# BoardC.net
KiCad netlist of a schematic drawn in Altium Designer
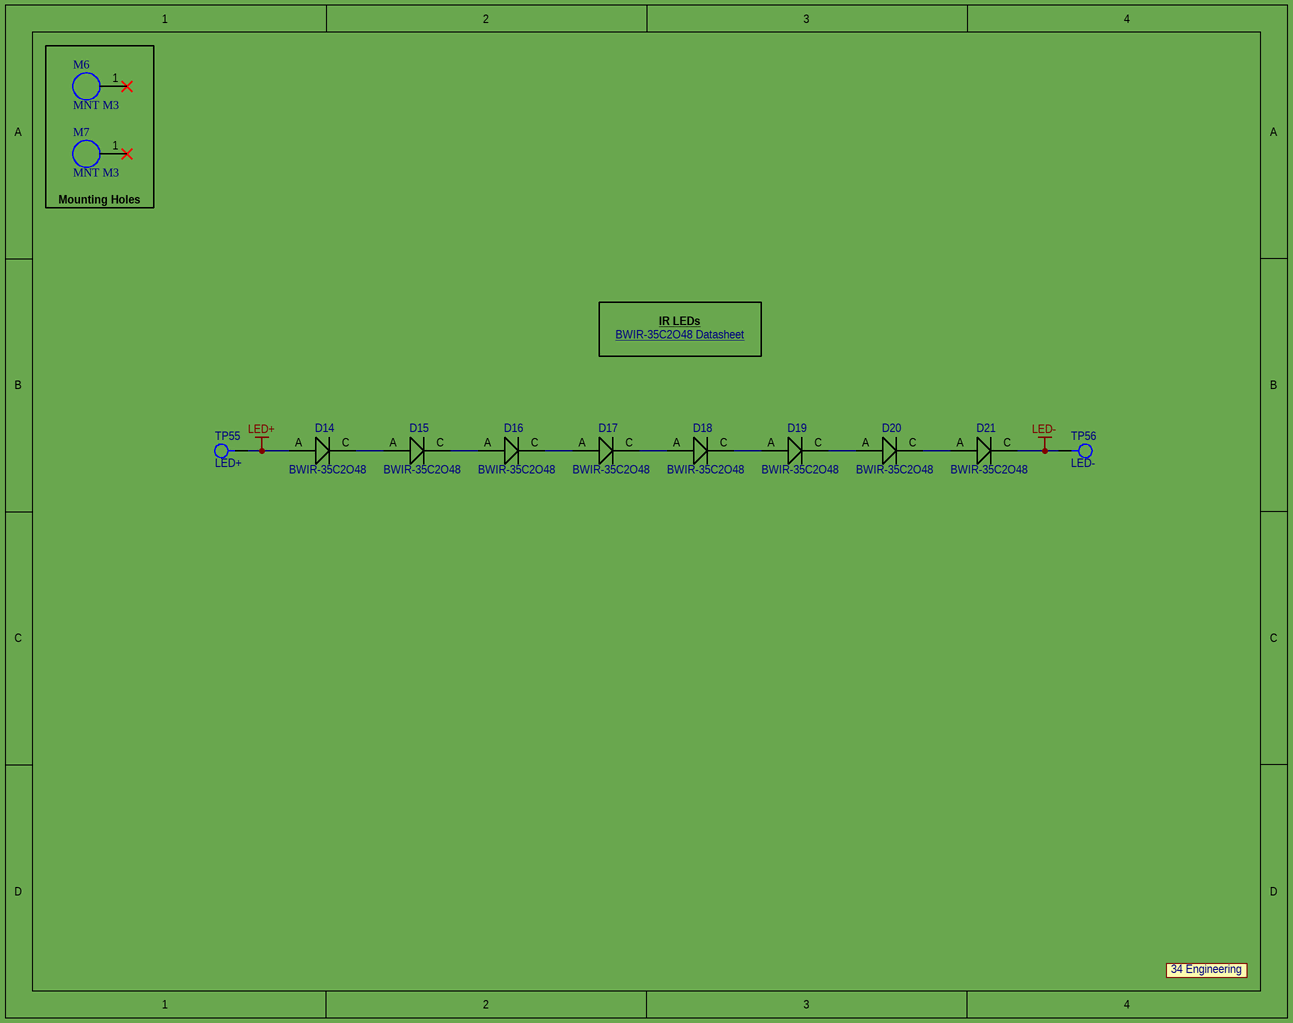
[diagram p0: BoardC.SchDoc]

(export (version "E")
  (design (tool "Eeschema 10.0.6"))
  (components
    (comp (ref "D14")
      (value "BWIR-35C2O48")
      (footprint "BWIR-35C2O48")
      (description "Infrared (IR) Emitter 850nm 1.7V 1A 260mW/sr @ 1A (Typ) 120° 1414 (3535 Metric)")
      (fields (field (name "MANUFACTURER") "American Bright"))
      (libsource (lib "Virtex") (part "BWIR-35C2O48"))
    )
    (comp (ref "D15")
      (value "BWIR-35C2O48")
      (footprint "BWIR-35C2O48")
      (description "Infrared (IR) Emitter 850nm 1.7V 1A 260mW/sr @ 1A (Typ) 120° 1414 (3535 Metric)")
      (fields (field (name "MANUFACTURER") "American Bright"))
      (libsource (lib "Virtex") (part "BWIR-35C2O48"))
    )
    (comp (ref "D16")
      (value "BWIR-35C2O48")
      (footprint "BWIR-35C2O48")
      (description "Infrared (IR) Emitter 850nm 1.7V 1A 260mW/sr @ 1A (Typ) 120° 1414 (3535 Metric)")
      (fields (field (name "MANUFACTURER") "American Bright"))
      (libsource (lib "Virtex") (part "BWIR-35C2O48"))
    )
    (comp (ref "D17")
      (value "BWIR-35C2O48")
      (footprint "BWIR-35C2O48")
      (description "Infrared (IR) Emitter 850nm 1.7V 1A 260mW/sr @ 1A (Typ) 120° 1414 (3535 Metric)")
      (fields (field (name "MANUFACTURER") "American Bright"))
      (libsource (lib "Virtex") (part "BWIR-35C2O48"))
    )
    (comp (ref "D18")
      (value "BWIR-35C2O48")
      (footprint "BWIR-35C2O48")
      (description "Infrared (IR) Emitter 850nm 1.7V 1A 260mW/sr @ 1A (Typ) 120° 1414 (3535 Metric)")
      (fields (field (name "MANUFACTURER") "American Bright"))
      (libsource (lib "Virtex") (part "BWIR-35C2O48"))
    )
    (comp (ref "D19")
      (value "BWIR-35C2O48")
      (footprint "BWIR-35C2O48")
      (description "Infrared (IR) Emitter 850nm 1.7V 1A 260mW/sr @ 1A (Typ) 120° 1414 (3535 Metric)")
      (fields (field (name "MANUFACTURER") "American Bright"))
      (libsource (lib "Virtex") (part "BWIR-35C2O48"))
    )
    (comp (ref "D20")
      (value "BWIR-35C2O48")
      (footprint "BWIR-35C2O48")
      (description "Infrared (IR) Emitter 850nm 1.7V 1A 260mW/sr @ 1A (Typ) 120° 1414 (3535 Metric)")
      (fields (field (name "MANUFACTURER") "American Bright"))
      (libsource (lib "Virtex") (part "BWIR-35C2O48"))
    )
    (comp (ref "D21")
      (value "BWIR-35C2O48")
      (footprint "BWIR-35C2O48")
      (description "Infrared (IR) Emitter 850nm 1.7V 1A 260mW/sr @ 1A (Typ) 120° 1414 (3535 Metric)")
      (fields (field (name "MANUFACTURER") "American Bright"))
      (libsource (lib "Virtex") (part "BWIR-35C2O48"))
    )
    (comp (ref "LOGO2")
      (value "34 Engineering Logo")
      (footprint "34EngineeringLogo")
      (description "34 Engineering Silkscreen Logo")
      (libsource (lib "Virtex") (part "34EngineeringLogo"))
    )
    (comp (ref "M6")
      (value "MNT M3")
      (footprint "MNT M3")
      (description "Mounting hole for an M3 bolt")
      (libsource (lib "Virtex") (part "MNT M3"))
    )
    (comp (ref "M7")
      (value "MNT M3")
      (footprint "MNT M3")
      (description "Mounting hole for an M3 bolt")
      (libsource (lib "Virtex") (part "MNT M3"))
    )
    (comp (ref "TP55")
      (value "LED+")
      (footprint "TestPoint1mm")
      (description "Test Point 1mm Diameter")
      (libsource (lib "Virtex") (part "TestPoint1mm"))
    )
    (comp (ref "TP56")
      (value "LED-")
      (footprint "TestPoint1mm")
      (description "Test Point 1mm Diameter")
      (libsource (lib "Virtex") (part "TestPoint1mm"))
    )
  )
  (nets
    (net (code "1") (name "LED+") (class "Default")
      (node (ref "D14") (pin "A") (pintype "power_in"))
      (node (ref "TP55") (pin "1") (pintype "passive"))
    )
    (net (code "2") (name "LED-") (class "Default")
      (node (ref "D21") (pin "C") (pintype "power_in"))
      (node (ref "TP56") (pin "1") (pintype "passive"))
    )
    (net (code "3") (name "Net-(D14-PadC)") (class "Default")
      (node (ref "D14") (pin "C") (pintype "power_in"))
      (node (ref "D15") (pin "A") (pintype "power_in"))
    )
    (net (code "4") (name "Net-(D15-PadC)") (class "Default")
      (node (ref "D15") (pin "C") (pintype "power_in"))
      (node (ref "D16") (pin "A") (pintype "power_in"))
    )
    (net (code "5") (name "Net-(D16-PadC)") (class "Default")
      (node (ref "D16") (pin "C") (pintype "power_in"))
      (node (ref "D17") (pin "A") (pintype "power_in"))
    )
    (net (code "6") (name "Net-(D17-PadC)") (class "Default")
      (node (ref "D17") (pin "C") (pintype "power_in"))
      (node (ref "D18") (pin "A") (pintype "power_in"))
    )
    (net (code "7") (name "Net-(D18-PadC)") (class "Default")
      (node (ref "D18") (pin "C") (pintype "power_in"))
      (node (ref "D19") (pin "A") (pintype "power_in"))
    )
    (net (code "8") (name "Net-(D19-PadC)") (class "Default")
      (node (ref "D19") (pin "C") (pintype "power_in"))
      (node (ref "D20") (pin "A") (pintype "power_in"))
    )
    (net (code "9") (name "Net-(D20-PadC)") (class "Default")
      (node (ref "D20") (pin "C") (pintype "power_in"))
      (node (ref "D21") (pin "A") (pintype "power_in"))
    )
    (net (code "10") (name "unconnected-(M6-Pad1)") (class "Default")
      (node (ref "M6") (pin "1") (pintype "passive+no_connect"))
    )
    (net (code "11") (name "unconnected-(M7-Pad1)") (class "Default")
      (node (ref "M7") (pin "1") (pintype "passive+no_connect"))
    )
  )
)
